# B.net
KiCad netlist of a schematic drawn in EAGLE
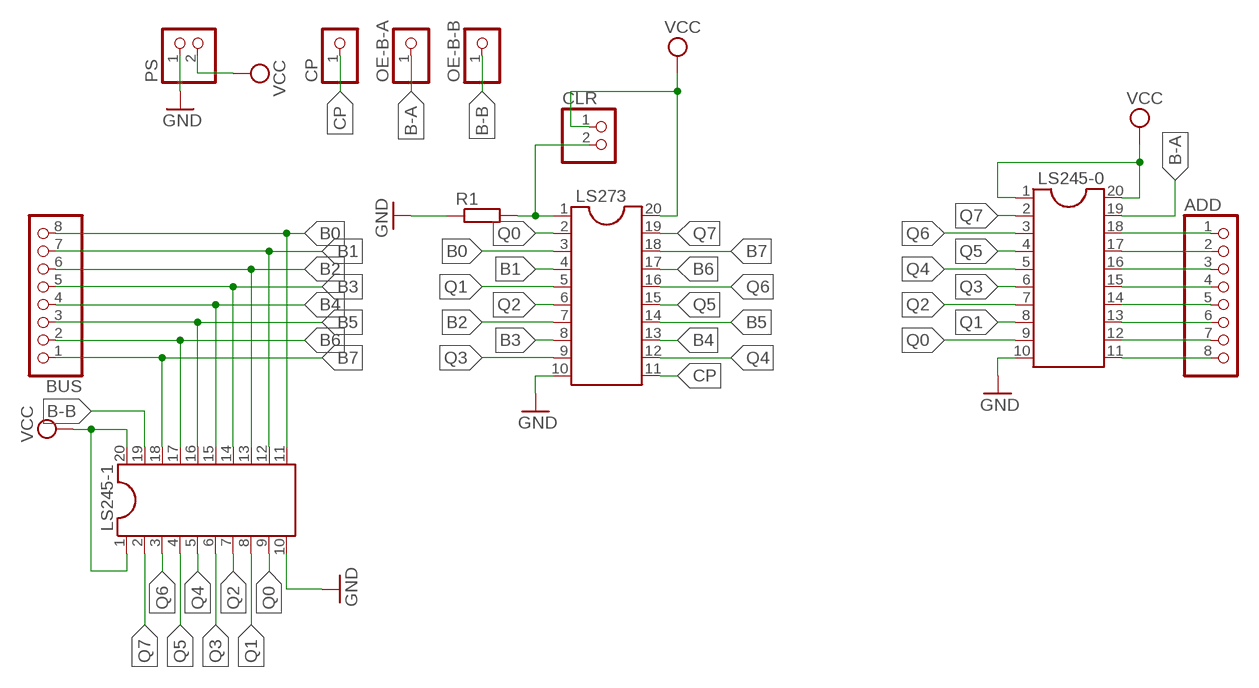
[diagram p0: schematic, sheet 1]

(export (version "E")
  (design (tool "Eeschema 10.0.6"))
  (components
    (comp (ref "ADD")
      (value "PINHD-1X8")
      (footprint "eagle-import:1X08")
      (libsource (lib "eagle-import") (part "PINHD-1X8"))
    )
    (comp (ref "BUS")
      (value "PINHD-1X8")
      (footprint "eagle-import:1X08")
      (libsource (lib "eagle-import") (part "PINHD-1X8"))
    )
    (comp (ref "CLR")
      (value "PINHD-1X2")
      (footprint "eagle-import:1X02")
      (libsource (lib "eagle-import") (part "PINHD-1X2"))
    )
    (comp (ref "CP")
      (value "PINHD-1X1")
      (footprint "eagle-import:1X01")
      (libsource (lib "eagle-import") (part "PINHD-1X1"))
    )
    (comp (ref "LS245-0")
      (value "DIL20S")
      (footprint "eagle-import:SOCKET-20")
      (libsource (lib "eagle-import") (part "DIL20S"))
    )
    (comp (ref "LS245-1")
      (value "DIL20S")
      (footprint "eagle-import:SOCKET-20")
      (libsource (lib "eagle-import") (part "DIL20S"))
    )
    (comp (ref "LS273")
      (value "DIL20S")
      (footprint "eagle-import:SOCKET-20")
      (libsource (lib "eagle-import") (part "DIL20S"))
    )
    (comp (ref "OE-B-A")
      (value "PINHD-1X1")
      (footprint "eagle-import:1X01")
      (libsource (lib "eagle-import") (part "PINHD-1X1"))
    )
    (comp (ref "OE-B-B")
      (value "PINHD-1X1")
      (footprint "eagle-import:1X01")
      (libsource (lib "eagle-import") (part "PINHD-1X1"))
    )
    (comp (ref "PS")
      (value "PINHD-1X2")
      (footprint "eagle-import:1X02")
      (libsource (lib "eagle-import") (part "PINHD-1X2"))
    )
    (comp (ref "R1")
      (value "R-EU_0204/7")
      (footprint "eagle-import:0204_7")
      (libsource (lib "eagle-import") (part "R-EU_0204/7"))
    )
  )
  (nets
    (net (code "1") (name "B-A") (class "Default")
      (node (ref "LS245-0") (pin "19") (pinfunction "19_19") (pintype "passive"))
      (node (ref "OE-B-A") (pin "1") (pinfunction "1_1") (pintype "passive"))
    )
    (net (code "2") (name "B-B") (class "Default")
      (node (ref "LS245-1") (pin "19") (pinfunction "19_19") (pintype "passive"))
      (node (ref "OE-B-B") (pin "1") (pinfunction "1_1") (pintype "passive"))
    )
    (net (code "3") (name "B0") (class "Default")
      (node (ref "BUS") (pin "8") (pinfunction "8_8") (pintype "passive"))
      (node (ref "LS245-1") (pin "11") (pinfunction "11_11") (pintype "passive"))
      (node (ref "LS273") (pin "3") (pinfunction "3_3") (pintype "passive"))
    )
    (net (code "4") (name "B1") (class "Default")
      (node (ref "BUS") (pin "7") (pinfunction "7_7") (pintype "passive"))
      (node (ref "LS245-1") (pin "12") (pinfunction "12_12") (pintype "passive"))
      (node (ref "LS273") (pin "4") (pinfunction "4_4") (pintype "passive"))
    )
    (net (code "5") (name "B2") (class "Default")
      (node (ref "BUS") (pin "6") (pinfunction "6_6") (pintype "passive"))
      (node (ref "LS245-1") (pin "13") (pinfunction "13_13") (pintype "passive"))
      (node (ref "LS273") (pin "7") (pinfunction "7_7") (pintype "passive"))
    )
    (net (code "6") (name "B3") (class "Default")
      (node (ref "BUS") (pin "5") (pinfunction "5_5") (pintype "passive"))
      (node (ref "LS245-1") (pin "14") (pinfunction "14_14") (pintype "passive"))
      (node (ref "LS273") (pin "8") (pinfunction "8_8") (pintype "passive"))
    )
    (net (code "7") (name "B4") (class "Default")
      (node (ref "BUS") (pin "4") (pinfunction "4_4") (pintype "passive"))
      (node (ref "LS245-1") (pin "15") (pinfunction "15_15") (pintype "passive"))
      (node (ref "LS273") (pin "13") (pinfunction "13_13") (pintype "passive"))
    )
    (net (code "8") (name "B5") (class "Default")
      (node (ref "BUS") (pin "3") (pinfunction "3_3") (pintype "passive"))
      (node (ref "LS245-1") (pin "16") (pinfunction "16_16") (pintype "passive"))
      (node (ref "LS273") (pin "14") (pinfunction "14_14") (pintype "passive"))
    )
    (net (code "9") (name "B6") (class "Default")
      (node (ref "BUS") (pin "2") (pinfunction "2_2") (pintype "passive"))
      (node (ref "LS245-1") (pin "17") (pinfunction "17_17") (pintype "passive"))
      (node (ref "LS273") (pin "17") (pinfunction "17_17") (pintype "passive"))
    )
    (net (code "10") (name "B7") (class "Default")
      (node (ref "BUS") (pin "1") (pinfunction "1_1") (pintype "passive"))
      (node (ref "LS245-1") (pin "18") (pinfunction "18_18") (pintype "passive"))
      (node (ref "LS273") (pin "18") (pinfunction "18_18") (pintype "passive"))
    )
    (net (code "11") (name "CP") (class "Default")
      (node (ref "CP") (pin "1") (pinfunction "1_1") (pintype "passive"))
      (node (ref "LS273") (pin "11") (pinfunction "11_11") (pintype "passive"))
    )
    (net (code "12") (name "GND") (class "Default")
      (node (ref "LS245-0") (pin "10") (pinfunction "10_10") (pintype "passive"))
      (node (ref "LS245-1") (pin "10") (pinfunction "10_10") (pintype "passive"))
      (node (ref "LS273") (pin "10") (pinfunction "10_10") (pintype "passive"))
      (node (ref "PS") (pin "1") (pinfunction "1_1") (pintype "passive"))
      (node (ref "R1") (pin "1") (pinfunction "1_1") (pintype "passive"))
    )
    (net (code "13") (name "Net-(ADD-Pad1)") (class "Default")
      (node (ref "ADD") (pin "1") (pinfunction "1_1") (pintype "passive"))
      (node (ref "LS245-0") (pin "18") (pinfunction "18_18") (pintype "passive"))
    )
    (net (code "14") (name "Net-(ADD-Pad2)") (class "Default")
      (node (ref "ADD") (pin "2") (pinfunction "2_2") (pintype "passive"))
      (node (ref "LS245-0") (pin "17") (pinfunction "17_17") (pintype "passive"))
    )
    (net (code "15") (name "Net-(ADD-Pad3)") (class "Default")
      (node (ref "ADD") (pin "3") (pinfunction "3_3") (pintype "passive"))
      (node (ref "LS245-0") (pin "16") (pinfunction "16_16") (pintype "passive"))
    )
    (net (code "16") (name "Net-(ADD-Pad4)") (class "Default")
      (node (ref "ADD") (pin "4") (pinfunction "4_4") (pintype "passive"))
      (node (ref "LS245-0") (pin "15") (pinfunction "15_15") (pintype "passive"))
    )
    (net (code "17") (name "Net-(ADD-Pad5)") (class "Default")
      (node (ref "ADD") (pin "5") (pinfunction "5_5") (pintype "passive"))
      (node (ref "LS245-0") (pin "14") (pinfunction "14_14") (pintype "passive"))
    )
    (net (code "18") (name "Net-(ADD-Pad6)") (class "Default")
      (node (ref "ADD") (pin "6") (pinfunction "6_6") (pintype "passive"))
      (node (ref "LS245-0") (pin "13") (pinfunction "13_13") (pintype "passive"))
    )
    (net (code "19") (name "Net-(ADD-Pad7)") (class "Default")
      (node (ref "ADD") (pin "7") (pinfunction "7_7") (pintype "passive"))
      (node (ref "LS245-0") (pin "12") (pinfunction "12_12") (pintype "passive"))
    )
    (net (code "20") (name "Net-(ADD-Pad8)") (class "Default")
      (node (ref "ADD") (pin "8") (pinfunction "8_8") (pintype "passive"))
      (node (ref "LS245-0") (pin "11") (pinfunction "11_11") (pintype "passive"))
    )
    (net (code "21") (name "Net-(CLR-Pad2)") (class "Default")
      (node (ref "CLR") (pin "2") (pinfunction "2_2") (pintype "passive"))
      (node (ref "LS273") (pin "1") (pinfunction "1_1") (pintype "passive"))
      (node (ref "R1") (pin "2") (pinfunction "2_2") (pintype "passive"))
    )
    (net (code "22") (name "Q0") (class "Default")
      (node (ref "LS245-0") (pin "9") (pinfunction "9_9") (pintype "passive"))
      (node (ref "LS245-1") (pin "9") (pinfunction "9_9") (pintype "passive"))
      (node (ref "LS273") (pin "2") (pinfunction "2_2") (pintype "passive"))
    )
    (net (code "23") (name "Q1") (class "Default")
      (node (ref "LS245-0") (pin "8") (pinfunction "8_8") (pintype "passive"))
      (node (ref "LS245-1") (pin "8") (pinfunction "8_8") (pintype "passive"))
      (node (ref "LS273") (pin "5") (pinfunction "5_5") (pintype "passive"))
    )
    (net (code "24") (name "Q2") (class "Default")
      (node (ref "LS245-0") (pin "7") (pinfunction "7_7") (pintype "passive"))
      (node (ref "LS245-1") (pin "7") (pinfunction "7_7") (pintype "passive"))
      (node (ref "LS273") (pin "6") (pinfunction "6_6") (pintype "passive"))
    )
    (net (code "25") (name "Q3") (class "Default")
      (node (ref "LS245-0") (pin "6") (pinfunction "6_6") (pintype "passive"))
      (node (ref "LS245-1") (pin "6") (pinfunction "6_6") (pintype "passive"))
      (node (ref "LS273") (pin "9") (pinfunction "9_9") (pintype "passive"))
    )
    (net (code "26") (name "Q4") (class "Default")
      (node (ref "LS245-0") (pin "5") (pinfunction "5_5") (pintype "passive"))
      (node (ref "LS245-1") (pin "5") (pinfunction "5_5") (pintype "passive"))
      (node (ref "LS273") (pin "12") (pinfunction "12_12") (pintype "passive"))
    )
    (net (code "27") (name "Q5") (class "Default")
      (node (ref "LS245-0") (pin "4") (pinfunction "4_4") (pintype "passive"))
      (node (ref "LS245-1") (pin "4") (pinfunction "4_4") (pintype "passive"))
      (node (ref "LS273") (pin "15") (pinfunction "15_15") (pintype "passive"))
    )
    (net (code "28") (name "Q6") (class "Default")
      (node (ref "LS245-0") (pin "3") (pinfunction "3_3") (pintype "passive"))
      (node (ref "LS245-1") (pin "3") (pinfunction "3_3") (pintype "passive"))
      (node (ref "LS273") (pin "16") (pinfunction "16_16") (pintype "passive"))
    )
    (net (code "29") (name "Q7") (class "Default")
      (node (ref "LS245-0") (pin "2") (pinfunction "2_2") (pintype "passive"))
      (node (ref "LS245-1") (pin "2") (pinfunction "2_2") (pintype "passive"))
      (node (ref "LS273") (pin "19") (pinfunction "19_19") (pintype "passive"))
    )
    (net (code "30") (name "VCC") (class "Default")
      (node (ref "CLR") (pin "1") (pinfunction "1_1") (pintype "passive"))
      (node (ref "LS245-0") (pin "1") (pinfunction "1_1") (pintype "passive"))
      (node (ref "LS245-0") (pin "20") (pinfunction "20_20") (pintype "passive"))
      (node (ref "LS245-1") (pin "1") (pinfunction "1_1") (pintype "passive"))
      (node (ref "LS245-1") (pin "20") (pinfunction "20_20") (pintype "passive"))
      (node (ref "LS273") (pin "20") (pinfunction "20_20") (pintype "passive"))
      (node (ref "PS") (pin "2") (pinfunction "2_2") (pintype "passive"))
    )
  )
)
